# REMS.net
KiCad netlist of a schematic drawn in Altium Designer
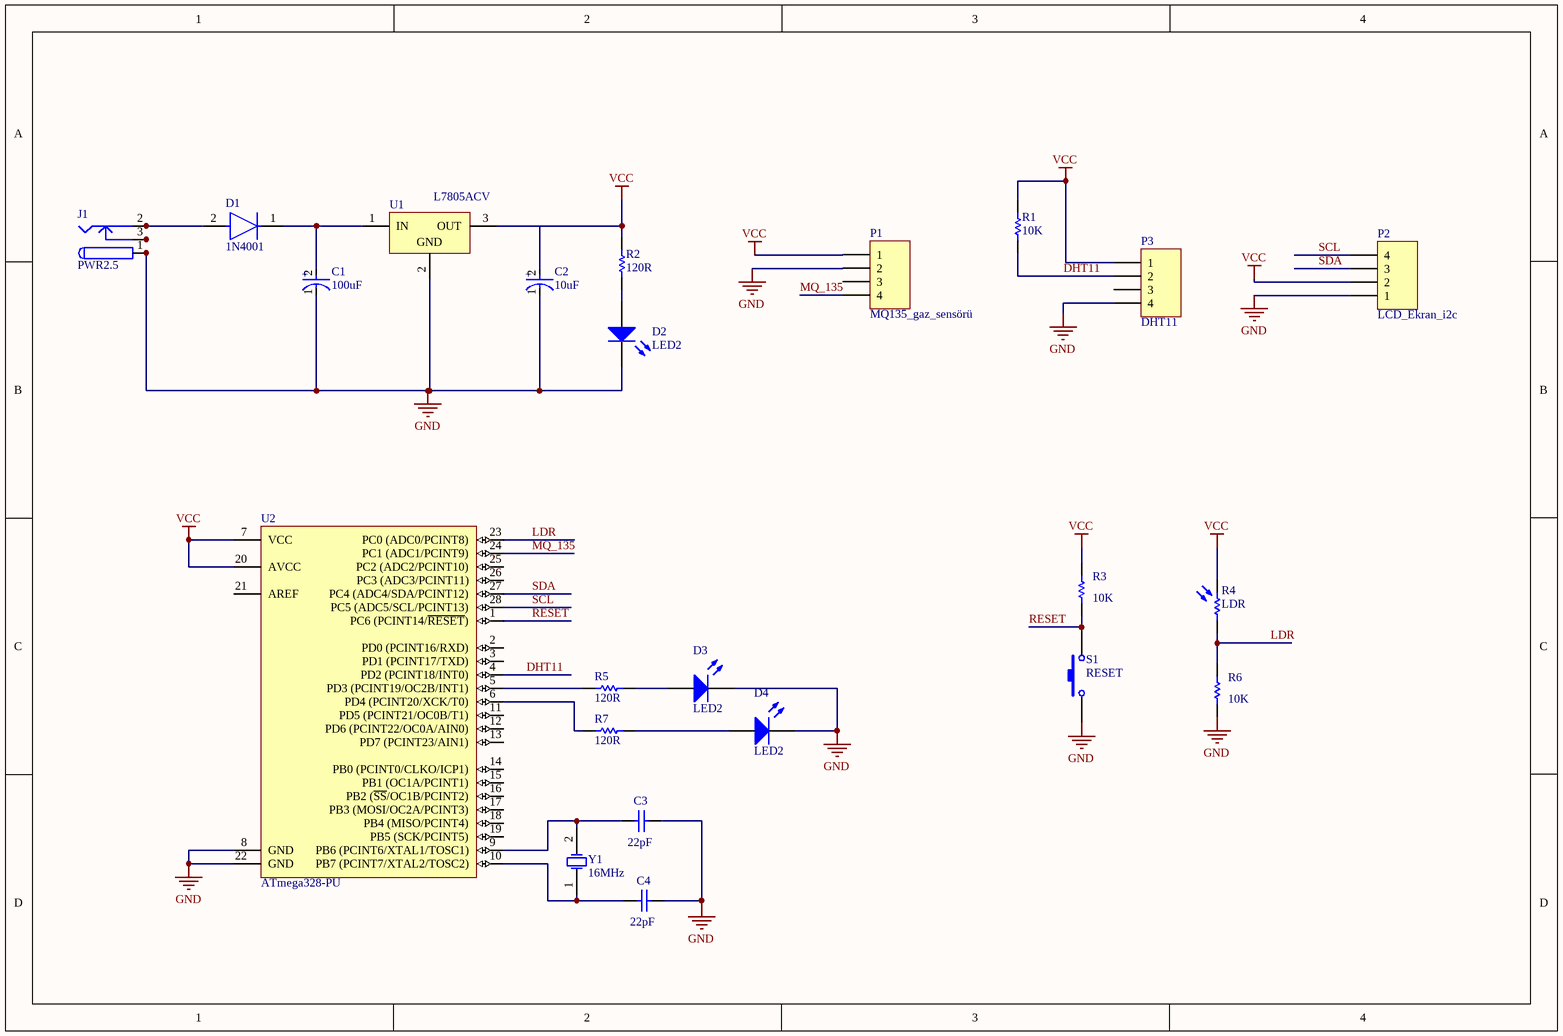
[diagram p0: REMS.SchDoc]

(export (version "E")
  (design (tool "Eeschema 10.0.6"))
  (components
    (comp (ref "C1")
      (value "100uF")
      (footprint "FP-RAD-TH-D_8_0_5-L_15_1-MFG")
      (description "Aluminum Electrolytic Capacitors (Radial Lead Type) 100uF ±20% 63V")
      (fields (field (name "TOLERANCE") "20%"))
      (libsource (lib "Altium Content Vault") (part "a00bbbee19879c290e62620ae7e47b1"))
    )
    (comp (ref "C2")
      (value "10uF")
      (footprint "FP-RAD-TH-D_5_0_5-L_11_1-MFG")
      (description "Aluminum Electrolytic Capacitors (Radial Lead Type) 10uF ±20% 63V")
      (fields (field (name "TOLERANCE") "20%") (field (name "VOLTAGE") "63V"))
      (libsource (lib "Altium Content Vault") (part "a00bbbee19879c290e62620ae7e47b1"))
    )
    (comp (ref "C3")
      (value "22pF")
      (footprint "mercimek")
      (description "Capacitor")
      (fields (field (name "PUBLISHER") "Altium Limited"))
      (libsource (lib "Miscellaneous Devices") (part "Cap"))
    )
    (comp (ref "C4")
      (value "22pF")
      (footprint "mercimek")
      (description "Capacitor")
      (fields (field (name "PUBLISHER") "Altium Limited"))
      (libsource (lib "Miscellaneous Devices") (part "Cap"))
    )
    (comp (ref "D1")
      (value "1N4001")
      (footprint "FP-DO-41-MFG")
      (description "DIODE GEN PURP 50V 1A DO41")
      (fields
        (field (name "MANUFACTURER PART NUMBER") "1N4001-TP")
        (field (name "MANUFACTURER") "Micro Commercial")
      )
      (libsource (lib "Altium Content Vault") (part "d7152d700b627762746794eb795d46e"))
    )
    (comp (ref "D2")
      (value "LED2")
      (footprint "3.2X1.6X1.1")
      (description "Typical RED, GREEN, YELLOW, AMBER GaAs LED")
      (fields (field (name "PUBLISHER") "Altium Limited"))
      (libsource (lib "Miscellaneous Devices") (part "LED2"))
    )
    (comp (ref "D3")
      (value "LED2")
      (footprint "3.2X1.6X1.1")
      (description "Typical RED, GREEN, YELLOW, AMBER GaAs LED")
      (fields (field (name "PUBLISHER") "Altium Limited"))
      (libsource (lib "Miscellaneous Devices") (part "LED2"))
    )
    (comp (ref "D4")
      (value "LED2")
      (footprint "3.2X1.6X1.1")
      (description "Typical RED, GREEN, YELLOW, AMBER GaAs LED")
      (fields (field (name "PUBLISHER") "Altium Limited"))
      (libsource (lib "Miscellaneous Devices") (part "LED2"))
    )
    (comp (ref "J1")
      (value "PWR2.5")
      (footprint "DC soket")
      (description "Low Voltage Power Supply Connector")
      (fields (field (name "PUBLISHER") "Altium Limited"))
      (libsource (lib "Miscellaneous Connectors") (part "PWR2.5"))
    )
    (comp (ref "P1")
      (value "MQ135_gaz_sensörü")
      (footprint "MQ_SENSOR")
      (description "Header, 4-Pin")
      (fields (field (name "PUBLISHER") "Altium Limited"))
      (libsource (lib "Miscellaneous Connectors") (part "MHDR1X4"))
    )
    (comp (ref "P2")
      (value "LCD_Ekran_i2c")
      (footprint "MQ_SENSOR")
      (description "Header, 4-Pin")
      (fields (field (name "PUBLISHER") "Altium Limited"))
      (libsource (lib "") (part "MHDR1X4_1"))
    )
    (comp (ref "P3")
      (value "DHT11")
      (footprint "DHT11_dik")
      (description "Header, 4-Pin")
      (fields (field (name "PUBLISHER") "Altium Limited"))
      (libsource (lib "Miscellaneous Connectors") (part "MHDR1X4"))
    )
    (comp (ref "R1")
      (value "10K")
      (footprint "direnc_axial_0.4")
      (description "Resistor")
      (fields (field (name "PUBLISHER") "Altium Limited"))
      (libsource (lib "Miscellaneous Devices") (part "Res1"))
    )
    (comp (ref "R2")
      (value "120R")
      (footprint "direnc_axial_0.4")
      (description "Resistor")
      (fields (field (name "PUBLISHER") "Altium Limited"))
      (libsource (lib "Miscellaneous Devices") (part "Res1"))
    )
    (comp (ref "R3")
      (value "10K")
      (footprint "direnc_axial_0.4")
      (description "Resistor")
      (fields (field (name "PUBLISHER") "Altium Limited"))
      (libsource (lib "Miscellaneous Devices") (part "Res1"))
    )
    (comp (ref "R4")
      (value "LDR")
      (footprint "EXCE-VT90N1")
      (description "Photoconductive Resistor, 200 kOhm, 100 V, 80 mW, -40 to 75 degC, 2-Pin THD, RoHS")
      (fields (field (name "MANUFACTURER") "Excelitas Technology"))
      (libsource (lib "Altium Content Vault") (part "PHOTO-RES-2"))
    )
    (comp (ref "R5")
      (value "120R")
      (footprint "direnc_axial_0.4")
      (description "Resistor")
      (fields (field (name "PUBLISHER") "Altium Limited"))
      (libsource (lib "Miscellaneous Devices") (part "Res1"))
    )
    (comp (ref "R6")
      (value "10K")
      (footprint "direnc_axial_0.4")
      (description "Resistor")
      (fields (field (name "PUBLISHER") "Altium Limited"))
      (libsource (lib "Miscellaneous Devices") (part "Res1"))
    )
    (comp (ref "R7")
      (value "120R")
      (footprint "direnc_axial_0.4")
      (description "Resistor")
      (fields (field (name "PUBLISHER") "Altium Limited"))
      (libsource (lib "Miscellaneous Devices") (part "Res1"))
    )
    (comp (ref "S1")
      (value "RESET")
      (footprint "pushButton5mm")
      (description "Switch")
      (fields (field (name "PUBLISHER") "Altium Limited"))
      (libsource (lib "Miscellaneous Devices") (part "SW-PB"))
    )
    (comp (ref "U1")
      (value "L7805ACV")
      (footprint "TO220")
      (description "Positive Voltage Regulator, 5V, 3-Pin TO-220")
      (libsource (lib "Altium Content Vault") (part "PM-REG-L4940-SIL3"))
    )
    (comp (ref "U2")
      (value "ATmega328-PU")
      (footprint "28P3")
      (libsource (lib "Altium Content Vault") (part "MC-8B-ATM48-IL28"))
    )
    (comp (ref "Y1")
      (value "16MHz")
      (footprint "xtal")
      (description "Crystal Oscillator")
      (fields (field (name "PUBLISHER") "Altium Limited"))
      (libsource (lib "Miscellaneous Devices") (part "XTAL"))
    )
  )
  (nets
    (net (code "1") (name "/DHT11") (class "Default")
      (node (ref "P3") (pin "2") (pinfunction "2_2") (pintype "passive"))
      (node (ref "R1") (pin "2") (pinfunction "2_2") (pintype "passive"))
      (node (ref "U2") (pin "4") (pinfunction "PD2_(PCINT18/INT0)_4") (pintype "bidirectional"))
    )
    (net (code "2") (name "/LDR") (class "Default")
      (node (ref "R4") (pin "1") (pinfunction "1_1") (pintype "passive"))
      (node (ref "R6") (pin "2") (pinfunction "2_2") (pintype "passive"))
      (node (ref "U2") (pin "23") (pinfunction "PC0_(ADC0/PCINT8)_23") (pintype "bidirectional"))
    )
    (net (code "3") (name "/MQ_135") (class "Default")
      (node (ref "P1") (pin "4") (pinfunction "4_4") (pintype "passive"))
      (node (ref "U2") (pin "24") (pinfunction "PC1_(ADC1/PCINT9)_24") (pintype "bidirectional"))
    )
    (net (code "4") (name "/RESET") (class "Default")
      (node (ref "R3") (pin "1") (pinfunction "1_1") (pintype "passive"))
      (node (ref "S1") (pin "2") (pinfunction "2_2") (pintype "passive"))
      (node (ref "U2") (pin "1") (pinfunction "PC6_(PCINT14/~{RESET})_1") (pintype "bidirectional"))
    )
    (net (code "5") (name "/SCL") (class "Default")
      (node (ref "P2") (pin "4") (pinfunction "4_4") (pintype "passive"))
      (node (ref "U2") (pin "28") (pinfunction "PC5_(ADC5/SCL/PCINT13)_28") (pintype "bidirectional"))
    )
    (net (code "6") (name "/SDA") (class "Default")
      (node (ref "P2") (pin "3") (pinfunction "3_3") (pintype "passive"))
      (node (ref "U2") (pin "27") (pinfunction "PC4_(ADC4/SDA/PCINT12)_27") (pintype "bidirectional"))
    )
    (net (code "7") (name "GND") (class "Default")
      (node (ref "C1") (pin "1") (pinfunction "C_1") (pintype "passive"))
      (node (ref "C2") (pin "1") (pinfunction "C_1") (pintype "passive"))
      (node (ref "C3") (pin "2") (pinfunction "2_2") (pintype "passive"))
      (node (ref "C4") (pin "2") (pinfunction "2_2") (pintype "passive"))
      (node (ref "D2") (pin "2") (pinfunction "K_2") (pintype "passive"))
      (node (ref "D3") (pin "2") (pinfunction "K_2") (pintype "passive"))
      (node (ref "D4") (pin "2") (pinfunction "K_2") (pintype "passive"))
      (node (ref "J1") (pin "1") (pinfunction "1_1") (pintype "power_in"))
      (node (ref "J1") (pin "1A") (pinfunction "1A_1A") (pintype "power_in"))
      (node (ref "J1") (pin "1B") (pinfunction "1B_1B") (pintype "power_in"))
      (node (ref "P1") (pin "2") (pinfunction "2_2") (pintype "passive"))
      (node (ref "P2") (pin "1") (pinfunction "1_1") (pintype "passive"))
      (node (ref "P3") (pin "4") (pinfunction "4_4") (pintype "passive"))
      (node (ref "R6") (pin "1") (pinfunction "1_1") (pintype "passive"))
      (node (ref "S1") (pin "1") (pinfunction "1_1") (pintype "passive"))
      (node (ref "U1") (pin "2") (pinfunction "GND_2") (pintype "power_in"))
      (node (ref "U2") (pin "22") (pinfunction "GND_22") (pintype "power_in"))
      (node (ref "U2") (pin "8") (pinfunction "GND_8") (pintype "power_in"))
    )
    (net (code "8") (name "Net-(C1-A)") (class "Default")
      (node (ref "C1") (pin "2") (pinfunction "A_2") (pintype "passive"))
      (node (ref "D1") (pin "1") (pinfunction "C_1") (pintype "passive"))
      (node (ref "U1") (pin "1") (pinfunction "IN_1") (pintype "power_in"))
    )
    (net (code "9") (name "Net-(D1-A)") (class "Default")
      (node (ref "D1") (pin "2") (pinfunction "A_2") (pintype "passive"))
      (node (ref "J1") (pin "2") (pinfunction "2_2") (pintype "power_in"))
      (node (ref "J1") (pin "2A") (pinfunction "2A_2A") (pintype "power_in"))
      (node (ref "J1") (pin "2B") (pinfunction "2B_2B") (pintype "power_in"))
    )
    (net (code "10") (name "Net-(D2-A)") (class "Default")
      (node (ref "D2") (pin "1") (pinfunction "A_1") (pintype "passive"))
      (node (ref "R2") (pin "2") (pinfunction "2_2") (pintype "passive"))
    )
    (net (code "11") (name "Net-(D3-A)") (class "Default")
      (node (ref "D3") (pin "1") (pinfunction "A_1") (pintype "passive"))
      (node (ref "R5") (pin "2") (pinfunction "2_2") (pintype "passive"))
    )
    (net (code "12") (name "Net-(D4-A)") (class "Default")
      (node (ref "D4") (pin "1") (pinfunction "A_1") (pintype "passive"))
      (node (ref "R7") (pin "2") (pinfunction "2_2") (pintype "passive"))
    )
    (net (code "13") (name "Net-(J1-Pad3)") (class "Default")
      (node (ref "J1") (pin "3") (pinfunction "3_3") (pintype "power_in"))
      (node (ref "J1") (pin "3A") (pinfunction "3A_3A") (pintype "power_in"))
      (node (ref "J1") (pin "3B") (pinfunction "3B_3B") (pintype "power_in"))
    )
    (net (code "14") (name "Net-(U2-PB6_(PCINT6{slash}XTAL1{slash}TOSC1))") (class "Default")
      (node (ref "C3") (pin "1") (pinfunction "1_1") (pintype "passive"))
      (node (ref "U2") (pin "9") (pinfunction "PB6_(PCINT6/XTAL1/TOSC1)_9") (pintype "bidirectional"))
      (node (ref "Y1") (pin "2") (pinfunction "OSC2_2") (pintype "passive"))
    )
    (net (code "15") (name "Net-(U2-PB7_(PCINT7{slash}XTAL2{slash}TOSC2))") (class "Default")
      (node (ref "C4") (pin "1") (pinfunction "1_1") (pintype "passive"))
      (node (ref "U2") (pin "10") (pinfunction "PB7_(PCINT7/XTAL2/TOSC2)_10") (pintype "bidirectional"))
      (node (ref "Y1") (pin "1") (pinfunction "OSC1_1") (pintype "passive"))
    )
    (net (code "16") (name "Net-(U2-PD3_(PCINT19{slash}OC2B{slash}INT1))") (class "Default")
      (node (ref "R5") (pin "1") (pinfunction "1_1") (pintype "passive"))
      (node (ref "U2") (pin "5") (pinfunction "PD3_(PCINT19/OC2B/INT1)_5") (pintype "bidirectional"))
    )
    (net (code "17") (name "Net-(U2-PD4_(PCINT20{slash}XCK{slash}T0))") (class "Default")
      (node (ref "R7") (pin "1") (pinfunction "1_1") (pintype "passive"))
      (node (ref "U2") (pin "6") (pinfunction "PD4_(PCINT20/XCK/T0)_6") (pintype "bidirectional"))
    )
    (net (code "18") (name "VCC") (class "Default")
      (node (ref "C2") (pin "2") (pinfunction "A_2") (pintype "passive"))
      (node (ref "P1") (pin "1") (pinfunction "1_1") (pintype "passive"))
      (node (ref "P2") (pin "2") (pinfunction "2_2") (pintype "passive"))
      (node (ref "P3") (pin "1") (pinfunction "1_1") (pintype "passive"))
      (node (ref "R1") (pin "1") (pinfunction "1_1") (pintype "passive"))
      (node (ref "R2") (pin "1") (pinfunction "1_1") (pintype "passive"))
      (node (ref "R3") (pin "2") (pinfunction "2_2") (pintype "passive"))
      (node (ref "R4") (pin "2") (pinfunction "2_2") (pintype "passive"))
      (node (ref "U1") (pin "3") (pinfunction "OUT_3") (pintype "power_in"))
      (node (ref "U2") (pin "20") (pinfunction "AVCC_20") (pintype "power_in"))
      (node (ref "U2") (pin "7") (pinfunction "VCC_7") (pintype "power_in"))
    )
    (net (code "19") (name "unconnected-(P1-Pad3)") (class "Default")
      (node (ref "P1") (pin "3") (pinfunction "3_3") (pintype "passive"))
    )
    (net (code "20") (name "unconnected-(P3-Pad3)") (class "Default")
      (node (ref "P3") (pin "3") (pinfunction "3_3") (pintype "passive"))
    )
    (net (code "21") (name "unconnected-(U2-AREF-Pad21)") (class "Default")
      (node (ref "U2") (pin "21") (pinfunction "AREF_21") (pintype "power_in"))
    )
    (net (code "22") (name "unconnected-(U2-PB0_(PCINT0{slash}CLKO{slash}ICP1)-Pad14)") (class "Default")
      (node (ref "U2") (pin "14") (pinfunction "PB0_(PCINT0/CLKO/ICP1)_14") (pintype "bidirectional"))
    )
    (net (code "23") (name "unconnected-(U2-PB1_(OC1A{slash}PCINT1)-Pad15)") (class "Default")
      (node (ref "U2") (pin "15") (pinfunction "PB1_(OC1A/PCINT1)_15") (pintype "bidirectional"))
    )
    (net (code "24") (name "unconnected-(U2-PB2_(~{SS}{slash}OC1B{slash}PCINT2)-Pad16)") (class "Default")
      (node (ref "U2") (pin "16") (pinfunction "PB2_(~{SS}/OC1B/PCINT2)_16") (pintype "bidirectional"))
    )
    (net (code "25") (name "unconnected-(U2-PB3_(MOSI{slash}OC2A{slash}PCINT3)-Pad17)") (class "Default")
      (node (ref "U2") (pin "17") (pinfunction "PB3_(MOSI/OC2A/PCINT3)_17") (pintype "bidirectional"))
    )
    (net (code "26") (name "unconnected-(U2-PB4_(MISO{slash}PCINT4)-Pad18)") (class "Default")
      (node (ref "U2") (pin "18") (pinfunction "PB4_(MISO/PCINT4)_18") (pintype "bidirectional"))
    )
    (net (code "27") (name "unconnected-(U2-PB5_(SCK{slash}PCINT5)-Pad19)") (class "Default")
      (node (ref "U2") (pin "19") (pinfunction "PB5_(SCK/PCINT5)_19") (pintype "bidirectional"))
    )
    (net (code "28") (name "unconnected-(U2-PC2_(ADC2{slash}PCINT10)-Pad25)") (class "Default")
      (node (ref "U2") (pin "25") (pinfunction "PC2_(ADC2/PCINT10)_25") (pintype "bidirectional"))
    )
    (net (code "29") (name "unconnected-(U2-PC3_(ADC3{slash}PCINT11)-Pad26)") (class "Default")
      (node (ref "U2") (pin "26") (pinfunction "PC3_(ADC3/PCINT11)_26") (pintype "bidirectional"))
    )
    (net (code "30") (name "unconnected-(U2-PD0_(PCINT16{slash}RXD)-Pad2)") (class "Default")
      (node (ref "U2") (pin "2") (pinfunction "PD0_(PCINT16/RXD)_2") (pintype "bidirectional"))
    )
    (net (code "31") (name "unconnected-(U2-PD1_(PCINT17{slash}TXD)-Pad3)") (class "Default")
      (node (ref "U2") (pin "3") (pinfunction "PD1_(PCINT17/TXD)_3") (pintype "bidirectional"))
    )
    (net (code "32") (name "unconnected-(U2-PD5_(PCINT21{slash}OC0B{slash}T1)-Pad11)") (class "Default")
      (node (ref "U2") (pin "11") (pinfunction "PD5_(PCINT21/OC0B/T1)_11") (pintype "bidirectional"))
    )
    (net (code "33") (name "unconnected-(U2-PD6_(PCINT22{slash}OC0A{slash}AIN0)-Pad12)") (class "Default")
      (node (ref "U2") (pin "12") (pinfunction "PD6_(PCINT22/OC0A/AIN0)_12") (pintype "bidirectional"))
    )
    (net (code "34") (name "unconnected-(U2-PD7_(PCINT23{slash}AIN1)-Pad13)") (class "Default")
      (node (ref "U2") (pin "13") (pinfunction "PD7_(PCINT23/AIN1)_13") (pintype "bidirectional"))
    )
  )
)
